# alarm_clock.net
KiCad netlist of a schematic drawn in Altium Designer
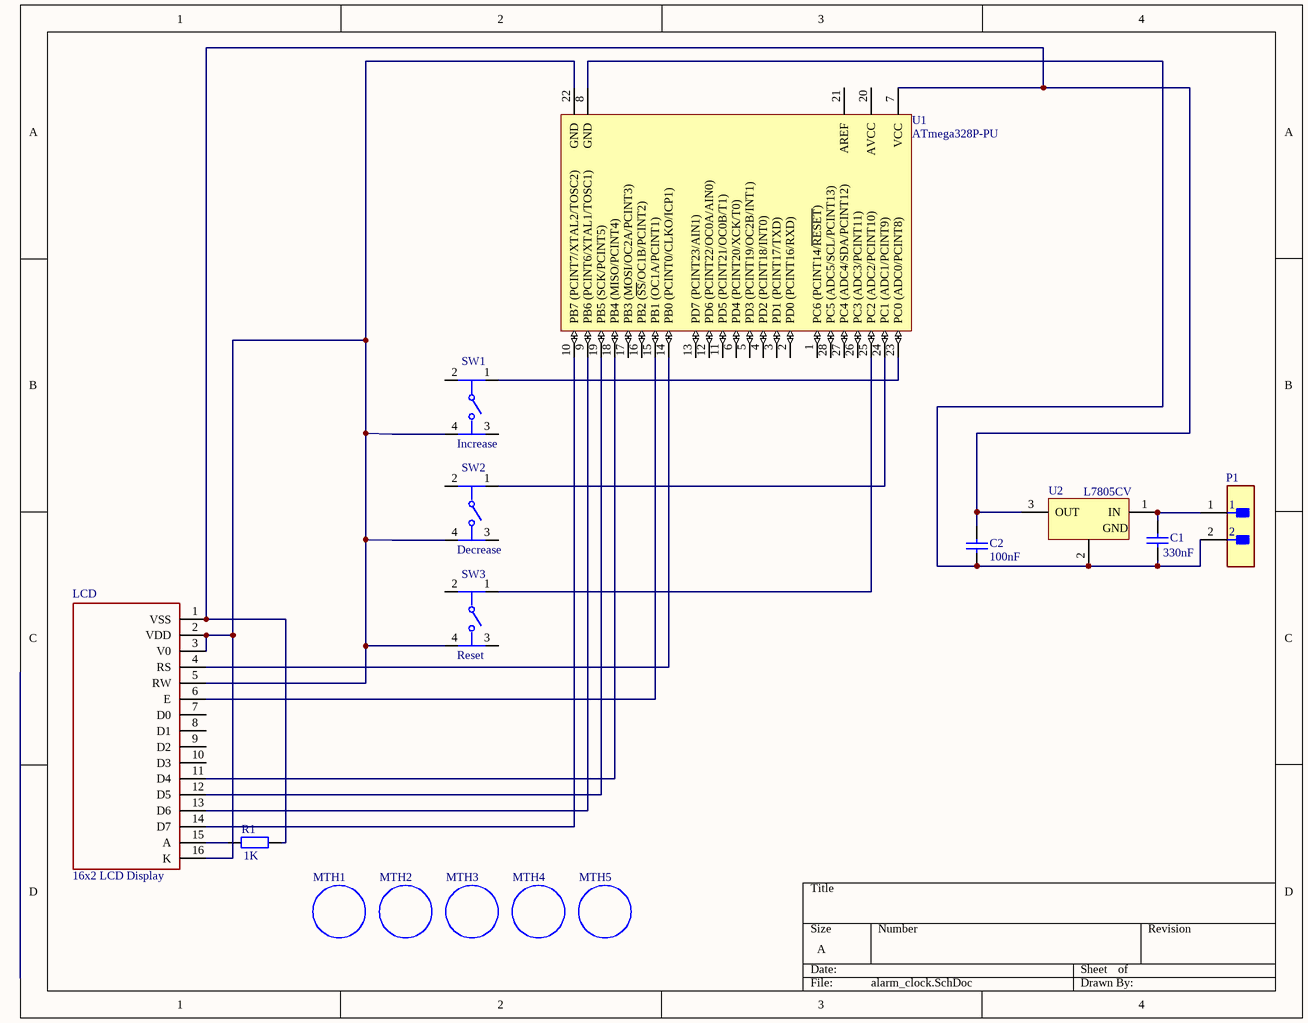
[diagram p0: alarm_clock.SchDoc]

(export (version "E")
  (design (tool "Eeschema 10.0.6"))
  (components
    (comp (ref "C1")
      (value "330nF")
      (footprint "RAD-0.3")
      (description "Capacitor")
      (fields (field (name "Comment") "Cap") (field (name "PUBLISHER") "Altium Limited"))
      (libsource (lib "Miscellaneous Devices") (part "Cap"))
    )
    (comp (ref "C2")
      (value "100nF")
      (footprint "RAD-0.3")
      (description "Capacitor")
      (fields (field (name "Comment") "Cap") (field (name "PUBLISHER") "Altium Limited"))
      (libsource (lib "Miscellaneous Devices") (part "Cap"))
    )
    (comp (ref "LCD")
      (value "16x2 LCD Display")
      (footprint "LCD1602")
      (libsource (lib "alarm_clock") (part "LCD1602"))
    )
    (comp (ref "MTH1") (value "~") (footprint "MTH") (libsource (lib "alarm_clock") (part "MTH")))
    (comp (ref "MTH2") (value "~") (footprint "MTH") (libsource (lib "alarm_clock") (part "MTH")))
    (comp (ref "MTH3") (value "~") (footprint "MTH") (libsource (lib "alarm_clock") (part "MTH")))
    (comp (ref "MTH4") (value "~") (footprint "MTH") (libsource (lib "alarm_clock") (part "MTH")))
    (comp (ref "MTH5") (value "~") (footprint "MTH") (libsource (lib "alarm_clock") (part "MTH")))
    (comp (ref "P1")
      (value "B2B-XH-A(LF)(SN)")
      (footprint "FP-B2B-XH-A_LF_SN-MFG")
      (description "CONN HEADER VERT 2POS 2.5MM")
      (libsource (lib "Altium Content Vault") (part "3bc925449376181038e59eaffc5286c"))
    )
    (comp (ref "R1")
      (value "1K")
      (footprint "AXIAL-0.4")
      (description "Resistor")
      (fields (field (name "Comment") "Res2") (field (name "PUBLISHER") "Altium Limited"))
      (libsource (lib "Miscellaneous Devices") (part "Res2"))
    )
    (comp (ref "SW1")
      (value "Increase")
      (footprint "FP-1-1825910-0-MFG")
      (description "SWITCH TACTILE SPST-NO 0.05A 24V")
      (libsource (lib "Altium Content Vault") (part "b8895f3f4cefb76e1819d2863dba89b"))
    )
    (comp (ref "SW2")
      (value "Decrease")
      (footprint "FP-1-1825910-0-MFG")
      (description "SWITCH TACTILE SPST-NO 0.05A 24V")
      (libsource (lib "Altium Content Vault") (part "b8895f3f4cefb76e1819d2863dba89b"))
    )
    (comp (ref "SW3")
      (value "Reset")
      (footprint "FP-1-1825910-0-MFG")
      (description "SWITCH TACTILE SPST-NO 0.05A 24V")
      (libsource (lib "Altium Content Vault") (part "b8895f3f4cefb76e1819d2863dba89b"))
    )
    (comp (ref "U1")
      (value "ATmega328P-PU")
      (footprint "28P3")
      (libsource (lib "Altium Content Vault") (part "MC-8B-ATM48-IL28"))
    )
    (comp (ref "U2")
      (value "L7805CV")
      (footprint "TO220")
      (description "Positive Voltage Regulator, 5V, 3-Pin TO-220")
      (libsource (lib "Altium Content Vault") (part "PM-REG-L4940-SIL3"))
    )
  )
  (nets
    (net (code "1") (name "Net-(LCD-A)") (class "Default")
      (node (ref "LCD") (pin "15") (pinfunction "A_15") (pintype "passive"))
      (node (ref "R1") (pin "1") (pinfunction "1_1") (pintype "passive"))
    )
    (net (code "2") (name "Net-(LCD-D4)") (class "Default")
      (node (ref "LCD") (pin "11") (pinfunction "D4_11") (pintype "passive"))
      (node (ref "U1") (pin "18") (pinfunction "PB4_(MISO/PCINT4)_18") (pintype "bidirectional"))
    )
    (net (code "3") (name "Net-(LCD-D5)") (class "Default")
      (node (ref "LCD") (pin "12") (pinfunction "D5_12") (pintype "passive"))
      (node (ref "U1") (pin "19") (pinfunction "PB5_(SCK/PCINT5)_19") (pintype "bidirectional"))
    )
    (net (code "4") (name "Net-(LCD-D6)") (class "Default")
      (node (ref "LCD") (pin "13") (pinfunction "D6_13") (pintype "passive"))
      (node (ref "U1") (pin "9") (pinfunction "PB6_(PCINT6/XTAL1/TOSC1)_9") (pintype "bidirectional"))
    )
    (net (code "5") (name "Net-(LCD-D7)") (class "Default")
      (node (ref "LCD") (pin "14") (pinfunction "D7_14") (pintype "passive"))
      (node (ref "U1") (pin "10") (pinfunction "PB7_(PCINT7/XTAL2/TOSC2)_10") (pintype "bidirectional"))
    )
    (net (code "6") (name "Net-(LCD-E)") (class "Default")
      (node (ref "LCD") (pin "6") (pinfunction "E_6") (pintype "passive"))
      (node (ref "U1") (pin "15") (pinfunction "PB1_(OC1A/PCINT1)_15") (pintype "bidirectional"))
    )
    (net (code "7") (name "Net-(LCD-K)") (class "Default")
      (node (ref "LCD") (pin "16") (pinfunction "K_16") (pintype "passive"))
      (node (ref "LCD") (pin "2") (pinfunction "VDD_2") (pintype "passive"))
      (node (ref "LCD") (pin "3") (pinfunction "V0_3") (pintype "passive"))
      (node (ref "LCD") (pin "5") (pinfunction "RW_5") (pintype "passive"))
      (node (ref "SW1") (pin "4") (pinfunction "4_4") (pintype "passive"))
      (node (ref "SW2") (pin "4") (pinfunction "4_4") (pintype "passive"))
      (node (ref "SW3") (pin "4") (pinfunction "4_4") (pintype "passive"))
      (node (ref "U1") (pin "22") (pinfunction "GND_22") (pintype "power_in"))
    )
    (net (code "8") (name "Net-(LCD-RS)") (class "Default")
      (node (ref "LCD") (pin "4") (pinfunction "RS_4") (pintype "passive"))
      (node (ref "U1") (pin "14") (pinfunction "PB0_(PCINT0/CLKO/ICP1)_14") (pintype "bidirectional"))
    )
    (net (code "9") (name "Net-(LCD-VSS)") (class "Default")
      (node (ref "C2") (pin "2") (pinfunction "2_2") (pintype "passive"))
      (node (ref "LCD") (pin "1") (pinfunction "VSS_1") (pintype "passive"))
      (node (ref "R1") (pin "2") (pinfunction "2_2") (pintype "passive"))
      (node (ref "U1") (pin "7") (pinfunction "VCC_7") (pintype "power_in"))
      (node (ref "U2") (pin "3") (pinfunction "OUT_3") (pintype "power_in"))
    )
    (net (code "10") (name "Net-(U1-PC0_(ADC0{slash}PCINT8))") (class "Default")
      (node (ref "SW1") (pin "1") (pinfunction "1_1") (pintype "passive"))
      (node (ref "U1") (pin "23") (pinfunction "PC0_(ADC0/PCINT8)_23") (pintype "bidirectional"))
    )
    (net (code "11") (name "Net-(U1-PC1_(ADC1{slash}PCINT9))") (class "Default")
      (node (ref "SW2") (pin "1") (pinfunction "1_1") (pintype "passive"))
      (node (ref "U1") (pin "24") (pinfunction "PC1_(ADC1/PCINT9)_24") (pintype "bidirectional"))
    )
    (net (code "12") (name "Net-(U1-PC2_(ADC2{slash}PCINT10))") (class "Default")
      (node (ref "SW3") (pin "1") (pinfunction "1_1") (pintype "passive"))
      (node (ref "U1") (pin "25") (pinfunction "PC2_(ADC2/PCINT10)_25") (pintype "bidirectional"))
    )
    (net (code "13") (name "Net-(U2-GND)") (class "Default")
      (node (ref "C1") (pin "1") (pinfunction "1_1") (pintype "passive"))
      (node (ref "C2") (pin "1") (pinfunction "1_1") (pintype "passive"))
      (node (ref "P1") (pin "2") (pinfunction "2_2") (pintype "passive"))
      (node (ref "U1") (pin "8") (pinfunction "GND_8") (pintype "power_in"))
      (node (ref "U2") (pin "2") (pinfunction "GND_2") (pintype "power_in"))
    )
    (net (code "14") (name "Net-(U2-IN)") (class "Default")
      (node (ref "C1") (pin "2") (pinfunction "2_2") (pintype "passive"))
      (node (ref "P1") (pin "1") (pinfunction "1_1") (pintype "passive"))
      (node (ref "U2") (pin "1") (pinfunction "IN_1") (pintype "power_in"))
    )
    (net (code "15") (name "unconnected-(LCD-D0-Pad7)") (class "Default")
      (node (ref "LCD") (pin "7") (pinfunction "D0_7") (pintype "passive"))
    )
    (net (code "16") (name "unconnected-(LCD-D1-Pad8)") (class "Default")
      (node (ref "LCD") (pin "8") (pinfunction "D1_8") (pintype "passive"))
    )
    (net (code "17") (name "unconnected-(LCD-D2-Pad9)") (class "Default")
      (node (ref "LCD") (pin "9") (pinfunction "D2_9") (pintype "passive"))
    )
    (net (code "18") (name "unconnected-(LCD-D3-Pad10)") (class "Default")
      (node (ref "LCD") (pin "10") (pinfunction "D3_10") (pintype "passive"))
    )
    (net (code "19") (name "unconnected-(SW1-Pad2)") (class "Default")
      (node (ref "SW1") (pin "2") (pinfunction "2_2") (pintype "passive"))
    )
    (net (code "20") (name "unconnected-(SW1-Pad3)") (class "Default")
      (node (ref "SW1") (pin "3") (pinfunction "3_3") (pintype "passive"))
    )
    (net (code "21") (name "unconnected-(SW2-Pad2)") (class "Default")
      (node (ref "SW2") (pin "2") (pinfunction "2_2") (pintype "passive"))
    )
    (net (code "22") (name "unconnected-(SW2-Pad3)") (class "Default")
      (node (ref "SW2") (pin "3") (pinfunction "3_3") (pintype "passive"))
    )
    (net (code "23") (name "unconnected-(SW3-Pad2)") (class "Default")
      (node (ref "SW3") (pin "2") (pinfunction "2_2") (pintype "passive"))
    )
    (net (code "24") (name "unconnected-(SW3-Pad3)") (class "Default")
      (node (ref "SW3") (pin "3") (pinfunction "3_3") (pintype "passive"))
    )
    (net (code "25") (name "unconnected-(U1-AREF-Pad21)") (class "Default")
      (node (ref "U1") (pin "21") (pinfunction "AREF_21") (pintype "power_in"))
    )
    (net (code "26") (name "unconnected-(U1-AVCC-Pad20)") (class "Default")
      (node (ref "U1") (pin "20") (pinfunction "AVCC_20") (pintype "power_in"))
    )
    (net (code "27") (name "unconnected-(U1-PB2_(~{SS}{slash}OC1B{slash}PCINT2)-Pad16)") (class "Default")
      (node (ref "U1") (pin "16") (pinfunction "PB2_(~{SS}/OC1B/PCINT2)_16") (pintype "bidirectional"))
    )
    (net (code "28") (name "unconnected-(U1-PB3_(MOSI{slash}OC2A{slash}PCINT3)-Pad17)") (class "Default")
      (node (ref "U1") (pin "17") (pinfunction "PB3_(MOSI/OC2A/PCINT3)_17") (pintype "bidirectional"))
    )
    (net (code "29") (name "unconnected-(U1-PC3_(ADC3{slash}PCINT11)-Pad26)") (class "Default")
      (node (ref "U1") (pin "26") (pinfunction "PC3_(ADC3/PCINT11)_26") (pintype "bidirectional"))
    )
    (net (code "30") (name "unconnected-(U1-PC4_(ADC4{slash}SDA{slash}PCINT12)-Pad27)") (class "Default")
      (node (ref "U1") (pin "27") (pinfunction "PC4_(ADC4/SDA/PCINT12)_27") (pintype "bidirectional"))
    )
    (net (code "31") (name "unconnected-(U1-PC5_(ADC5{slash}SCL{slash}PCINT13)-Pad28)") (class "Default")
      (node (ref "U1") (pin "28") (pinfunction "PC5_(ADC5/SCL/PCINT13)_28") (pintype "bidirectional"))
    )
    (net (code "32") (name "unconnected-(U1-PC6_(PCINT14{slash}~{RESET})-Pad1)") (class "Default")
      (node (ref "U1") (pin "1") (pinfunction "PC6_(PCINT14/~{RESET})_1") (pintype "bidirectional"))
    )
    (net (code "33") (name "unconnected-(U1-PD0_(PCINT16{slash}RXD)-Pad2)") (class "Default")
      (node (ref "U1") (pin "2") (pinfunction "PD0_(PCINT16/RXD)_2") (pintype "bidirectional"))
    )
    (net (code "34") (name "unconnected-(U1-PD1_(PCINT17{slash}TXD)-Pad3)") (class "Default")
      (node (ref "U1") (pin "3") (pinfunction "PD1_(PCINT17/TXD)_3") (pintype "bidirectional"))
    )
    (net (code "35") (name "unconnected-(U1-PD2_(PCINT18{slash}INT0)-Pad4)") (class "Default")
      (node (ref "U1") (pin "4") (pinfunction "PD2_(PCINT18/INT0)_4") (pintype "bidirectional"))
    )
    (net (code "36") (name "unconnected-(U1-PD3_(PCINT19{slash}OC2B{slash}INT1)-Pad5)") (class "Default")
      (node (ref "U1") (pin "5") (pinfunction "PD3_(PCINT19/OC2B/INT1)_5") (pintype "bidirectional"))
    )
    (net (code "37") (name "unconnected-(U1-PD4_(PCINT20{slash}XCK{slash}T0)-Pad6)") (class "Default")
      (node (ref "U1") (pin "6") (pinfunction "PD4_(PCINT20/XCK/T0)_6") (pintype "bidirectional"))
    )
    (net (code "38") (name "unconnected-(U1-PD5_(PCINT21{slash}OC0B{slash}T1)-Pad11)") (class "Default")
      (node (ref "U1") (pin "11") (pinfunction "PD5_(PCINT21/OC0B/T1)_11") (pintype "bidirectional"))
    )
    (net (code "39") (name "unconnected-(U1-PD6_(PCINT22{slash}OC0A{slash}AIN0)-Pad12)") (class "Default")
      (node (ref "U1") (pin "12") (pinfunction "PD6_(PCINT22/OC0A/AIN0)_12") (pintype "bidirectional"))
    )
    (net (code "40") (name "unconnected-(U1-PD7_(PCINT23{slash}AIN1)-Pad13)") (class "Default")
      (node (ref "U1") (pin "13") (pinfunction "PD7_(PCINT23/AIN1)_13") (pintype "bidirectional"))
    )
  )
)
